# Send.net
KiCad netlist of a schematic drawn in Altium Designer
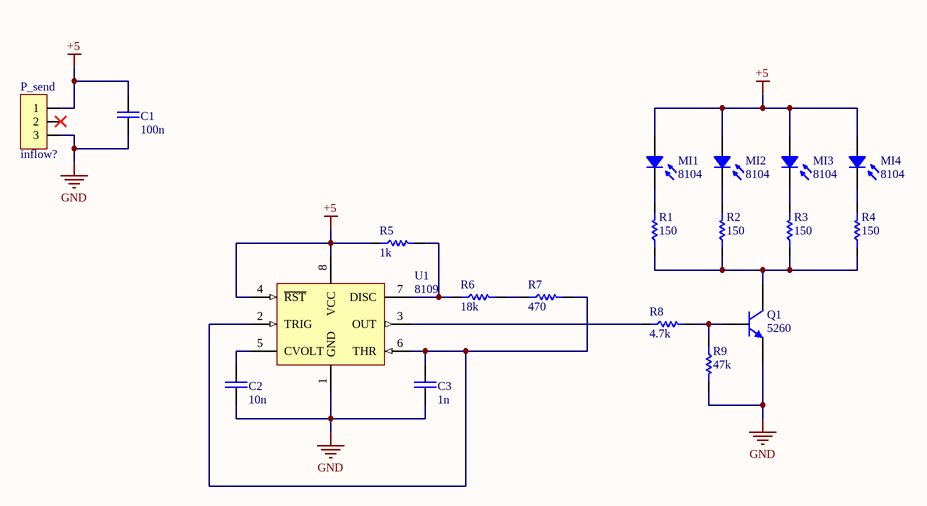
[diagram p0: Send.SchDoc]

(export (version "E")
  (design (tool "Eeschema 10.0.6"))
  (components
    (comp (ref "C1")
      (value "100n")
      (footprint "CAP 1206/3216")
      (description "Bipolar ceramic capacitor SMD")
      (fields (field (name "VALIDATION") "Valid"))
      (libsource (lib "aKaReZa") (part "Cap_Multi_SMD_1206"))
    )
    (comp (ref "C2")
      (value "10n")
      (footprint "CAP 1206/3216")
      (description "Bipolar ceramic capacitor SMD")
      (fields (field (name "VALIDATION") "Valid"))
      (libsource (lib "aKaReZa") (part "Cap_Multi_SMD_1206"))
    )
    (comp (ref "C3")
      (value "1n")
      (footprint "CAP 1206/3216")
      (description "Bipolar ceramic capacitor SMD")
      (fields (field (name "VALIDATION") "Valid"))
      (libsource (lib "aKaReZa") (part "Cap_Multi_SMD_1206"))
    )
    (comp (ref "MI1")
      (value "5'mm")
      (footprint "LED-5mm-IR Reciver")
      (description "Infra Red Reciever Photo Diode")
      (fields (field (name "INFLOW") "8104") (field (name "VALIDATION") "NT"))
      (libsource (lib "aKaReZa") (part "ModSen_IR_Reciever"))
    )
    (comp (ref "MI2")
      (value "5'mm")
      (footprint "LED-5mm-IR Reciver")
      (description "Infra Red Reciever Photo Diode")
      (fields (field (name "INFLOW") "8104") (field (name "VALIDATION") "NT"))
      (libsource (lib "aKaReZa") (part "ModSen_IR_Reciever"))
    )
    (comp (ref "MI3")
      (value "5'mm")
      (footprint "LED-5mm-IR Reciver")
      (description "Infra Red Reciever Photo Diode")
      (fields (field (name "INFLOW") "8104") (field (name "VALIDATION") "NT"))
      (libsource (lib "aKaReZa") (part "ModSen_IR_Reciever"))
    )
    (comp (ref "MI4")
      (value "5'mm")
      (footprint "LED-5mm-IR Reciver")
      (description "Infra Red Reciever Photo Diode")
      (fields (field (name "INFLOW") "8104") (field (name "VALIDATION") "NT"))
      (libsource (lib "aKaReZa") (part "ModSen_IR_Reciever"))
    )
    (comp (ref "P_send")
      (value "3'Pin")
      (footprint "MOLEX KK 0022272031")
      (description "Signal Connector 3'Pin")
      (fields (field (name "INFLOW") "inflow?") (field (name "VALIDATION") "Valid"))
      (libsource (lib "aKaReZa") (part "Con_Signal_3"))
    )
    (comp (ref "Q1")
      (value "NPN")
      (footprint "SOT23_N")
      (description "NPN Switching Transistors")
      (fields (field (name "INFLOW") "5260") (field (name "VALIDATION") "Valid"))
      (libsource (lib "aKaReZa") (part "Semi_BJT_2N2222_SMD"))
    )
    (comp (ref "R1")
      (value "150")
      (footprint "RES 1206 (3216X08L)")
      (description "Resistor")
      (fields (field (name "VALIDATION") "Valid"))
      (libsource (lib "aKaReZa") (part "Res_SMD_1206"))
    )
    (comp (ref "R2")
      (value "150")
      (footprint "RES 1206 (3216X08L)")
      (description "Resistor")
      (fields (field (name "VALIDATION") "Valid"))
      (libsource (lib "aKaReZa") (part "Res_SMD_1206"))
    )
    (comp (ref "R3")
      (value "150")
      (footprint "RES 1206 (3216X08L)")
      (description "Resistor")
      (fields (field (name "VALIDATION") "Valid"))
      (libsource (lib "aKaReZa") (part "Res_SMD_1206"))
    )
    (comp (ref "R4")
      (value "150")
      (footprint "RES 1206 (3216X08L)")
      (description "Resistor")
      (fields (field (name "VALIDATION") "Valid"))
      (libsource (lib "aKaReZa") (part "Res_SMD_1206"))
    )
    (comp (ref "R5")
      (value "1k")
      (footprint "RES 1206 (3216X08L)")
      (description "Resistor")
      (fields (field (name "VALIDATION") "Valid"))
      (libsource (lib "aKaReZa") (part "Res_SMD_1206"))
    )
    (comp (ref "R6")
      (value "18k")
      (footprint "RES 1206 (3216X08L)")
      (description "Resistor")
      (fields (field (name "VALIDATION") "Valid"))
      (libsource (lib "aKaReZa") (part "Res_SMD_1206"))
    )
    (comp (ref "R7")
      (value "470")
      (footprint "RES 1206 (3216X08L)")
      (description "Resistor")
      (fields (field (name "VALIDATION") "Valid"))
      (libsource (lib "aKaReZa") (part "Res_SMD_1206"))
    )
    (comp (ref "R8")
      (value "4.7k")
      (footprint "RES 1206 (3216X08L)")
      (description "Resistor")
      (fields (field (name "VALIDATION") "Valid"))
      (libsource (lib "aKaReZa") (part "Res_SMD_1206"))
    )
    (comp (ref "R9")
      (value "47k")
      (footprint "RES 1206 (3216X08L)")
      (description "Resistor")
      (fields (field (name "VALIDATION") "Valid"))
      (libsource (lib "aKaReZa") (part "Res_SMD_1206"))
    )
    (comp (ref "U1")
      (value "NE555")
      (footprint "SO8_narrow_n")
      (description "Astable or monostable operation timer")
      (fields (field (name "INFLOW") "8109") (field (name "VALIDATION") "Valid"))
      (libsource (lib "aKaReZa") (part "IC_TIM_NE555_SMD"))
    )
  )
  (nets
    (net (code "1") (name "+5") (class "Default")
      (node (ref "C1") (pin "1") (pinfunction "1_1") (pintype "passive"))
      (node (ref "MI1") (pin "1") (pinfunction "1_1") (pintype "passive"))
      (node (ref "MI2") (pin "1") (pinfunction "1_1") (pintype "passive"))
      (node (ref "MI3") (pin "1") (pinfunction "1_1") (pintype "passive"))
      (node (ref "MI4") (pin "1") (pinfunction "1_1") (pintype "passive"))
      (node (ref "P_send") (pin "1") (pinfunction "1_1") (pintype "passive"))
      (node (ref "R5") (pin "1") (pinfunction "1_1") (pintype "passive"))
      (node (ref "U1") (pin "4") (pinfunction "~{RST}_4") (pintype "input"))
      (node (ref "U1") (pin "8") (pinfunction "VCC_8") (pintype "power_in"))
    )
    (net (code "2") (name "GND") (class "Default")
      (node (ref "C1") (pin "2") (pinfunction "2_2") (pintype "passive"))
      (node (ref "C2") (pin "2") (pinfunction "2_2") (pintype "passive"))
      (node (ref "C3") (pin "2") (pinfunction "2_2") (pintype "passive"))
      (node (ref "P_send") (pin "3") (pinfunction "3_3") (pintype "passive"))
      (node (ref "Q1") (pin "2") (pinfunction "E_2") (pintype "passive"))
      (node (ref "R9") (pin "2") (pinfunction "2_2") (pintype "passive"))
      (node (ref "U1") (pin "1") (pinfunction "GND_1") (pintype "power_in"))
    )
    (net (code "3") (name "Net-(MI1-Pad2)") (class "Default")
      (node (ref "MI1") (pin "2") (pinfunction "2_2") (pintype "passive"))
      (node (ref "R1") (pin "2") (pinfunction "2_2") (pintype "passive"))
    )
    (net (code "4") (name "Net-(MI2-Pad2)") (class "Default")
      (node (ref "MI2") (pin "2") (pinfunction "2_2") (pintype "passive"))
      (node (ref "R2") (pin "2") (pinfunction "2_2") (pintype "passive"))
    )
    (net (code "5") (name "Net-(MI3-Pad2)") (class "Default")
      (node (ref "MI3") (pin "2") (pinfunction "2_2") (pintype "passive"))
      (node (ref "R3") (pin "2") (pinfunction "2_2") (pintype "passive"))
    )
    (net (code "6") (name "Net-(MI4-Pad2)") (class "Default")
      (node (ref "MI4") (pin "2") (pinfunction "2_2") (pintype "passive"))
      (node (ref "R4") (pin "2") (pinfunction "2_2") (pintype "passive"))
    )
    (net (code "7") (name "Net-(Q1-B)") (class "Default")
      (node (ref "Q1") (pin "1") (pinfunction "B_1") (pintype "passive"))
      (node (ref "R8") (pin "2") (pinfunction "2_2") (pintype "passive"))
      (node (ref "R9") (pin "1") (pinfunction "1_1") (pintype "passive"))
    )
    (net (code "8") (name "Net-(Q1-C)") (class "Default")
      (node (ref "Q1") (pin "3") (pinfunction "C_3") (pintype "passive"))
      (node (ref "R1") (pin "1") (pinfunction "1_1") (pintype "passive"))
      (node (ref "R2") (pin "1") (pinfunction "1_1") (pintype "passive"))
      (node (ref "R3") (pin "1") (pinfunction "1_1") (pintype "passive"))
      (node (ref "R4") (pin "1") (pinfunction "1_1") (pintype "passive"))
    )
    (net (code "9") (name "Net-(R6-Pad2)") (class "Default")
      (node (ref "R6") (pin "2") (pinfunction "2_2") (pintype "passive"))
      (node (ref "R7") (pin "1") (pinfunction "1_1") (pintype "passive"))
    )
    (net (code "10") (name "Net-(U1-CVOLT)") (class "Default")
      (node (ref "C2") (pin "1") (pinfunction "1_1") (pintype "passive"))
      (node (ref "U1") (pin "5") (pinfunction "CVOLT_5") (pintype "passive"))
    )
    (net (code "11") (name "Net-(U1-DISC)") (class "Default")
      (node (ref "R5") (pin "2") (pinfunction "2_2") (pintype "passive"))
      (node (ref "R6") (pin "1") (pinfunction "1_1") (pintype "passive"))
      (node (ref "U1") (pin "7") (pinfunction "DISC_7") (pintype "open_collector"))
    )
    (net (code "12") (name "Net-(U1-OUT)") (class "Default")
      (node (ref "R8") (pin "1") (pinfunction "1_1") (pintype "passive"))
      (node (ref "U1") (pin "3") (pinfunction "OUT_3") (pintype "output"))
    )
    (net (code "13") (name "Net-(U1-THR)") (class "Default")
      (node (ref "C3") (pin "1") (pinfunction "1_1") (pintype "passive"))
      (node (ref "R7") (pin "2") (pinfunction "2_2") (pintype "passive"))
      (node (ref "U1") (pin "2") (pinfunction "TRIG_2") (pintype "input"))
      (node (ref "U1") (pin "6") (pinfunction "THR_6") (pintype "input"))
    )
    (net (code "14") (name "unconnected-(P_send-Pad2)") (class "Default")
      (node (ref "P_send") (pin "2") (pinfunction "2_2") (pintype "passive+no_connect"))
    )
  )
)
